# proc2.net
KiCad netlist of a schematic drawn in EAGLE
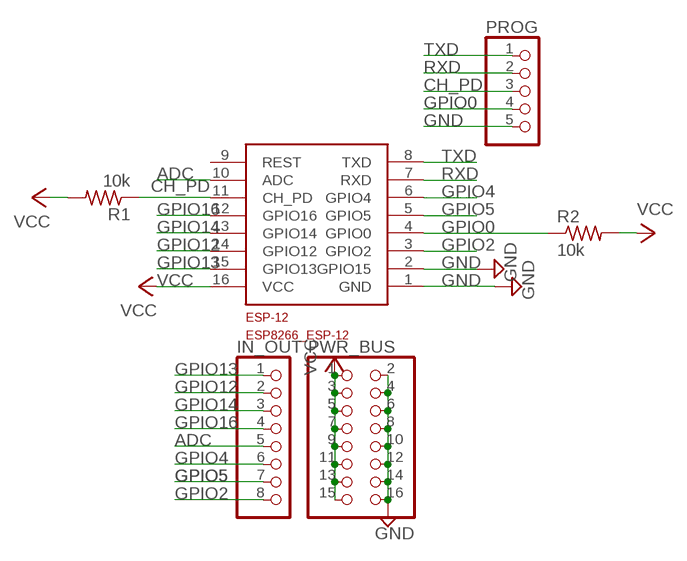
[diagram p0: schematic, sheet 1]

(export (version "E")
  (design (tool "Eeschema 10.0.6"))
  (components
    (comp (ref "ESP-12")
      (value "ESP8266_ESP-12")
      (footprint "eagle-import:ESP8266-ESP12")
      (libsource (lib "eagle-import") (part "ESP8266_ESP-12"))
    )
    (comp (ref "IN_OUT")
      (value "PINHD-1X8")
      (footprint "eagle-import:1X08")
      (libsource (lib "eagle-import") (part "PINHD-1X8"))
    )
    (comp (ref "PROG")
      (value "PINHD-1X5")
      (footprint "eagle-import:1X05")
      (libsource (lib "eagle-import") (part "PINHD-1X5"))
    )
    (comp (ref "PWR_BUS")
      (value "PINHD-2X8")
      (footprint "eagle-import:2X08")
      (libsource (lib "eagle-import") (part "PINHD-2X8"))
    )
    (comp (ref "R1")
      (value "10k")
      (footprint "eagle-import:M1206")
      (libsource (lib "eagle-import") (part "R-US_M1206"))
    )
    (comp (ref "R2")
      (value "10k")
      (footprint "eagle-import:M1206")
      (libsource (lib "eagle-import") (part "R-US_M1206"))
    )
  )
  (nets
    (net (code "1") (name "/ADC") (class "Default")
      (node (ref "ESP-12") (pin "10") (pinfunction "ADC_10") (pintype "bidirectional"))
      (node (ref "IN_OUT") (pin "5") (pinfunction "5_5") (pintype "passive"))
    )
    (net (code "2") (name "/CH_PD") (class "Default")
      (node (ref "ESP-12") (pin "11") (pinfunction "CH_PD_11") (pintype "bidirectional"))
      (node (ref "PROG") (pin "3") (pinfunction "3_3") (pintype "passive"))
      (node (ref "R1") (pin "1") (pinfunction "1_1") (pintype "passive"))
    )
    (net (code "3") (name "/GPIO0") (class "Default")
      (node (ref "ESP-12") (pin "4") (pinfunction "GPIO0_4") (pintype "bidirectional"))
      (node (ref "PROG") (pin "4") (pinfunction "4_4") (pintype "passive"))
      (node (ref "R2") (pin "1") (pinfunction "1_1") (pintype "passive"))
    )
    (net (code "4") (name "/GPIO2") (class "Default")
      (node (ref "ESP-12") (pin "3") (pinfunction "GPIO2_3") (pintype "bidirectional"))
      (node (ref "IN_OUT") (pin "8") (pinfunction "8_8") (pintype "passive"))
    )
    (net (code "5") (name "/GPIO4") (class "Default")
      (node (ref "ESP-12") (pin "6") (pinfunction "GPIO4_6") (pintype "bidirectional"))
      (node (ref "IN_OUT") (pin "6") (pinfunction "6_6") (pintype "passive"))
    )
    (net (code "6") (name "/GPIO5") (class "Default")
      (node (ref "ESP-12") (pin "5") (pinfunction "GPIO5_5") (pintype "bidirectional"))
      (node (ref "IN_OUT") (pin "7") (pinfunction "7_7") (pintype "passive"))
    )
    (net (code "7") (name "/GPIO12") (class "Default")
      (node (ref "ESP-12") (pin "14") (pinfunction "GPIO12_14") (pintype "bidirectional"))
      (node (ref "IN_OUT") (pin "2") (pinfunction "2_2") (pintype "passive"))
    )
    (net (code "8") (name "/GPIO13") (class "Default")
      (node (ref "ESP-12") (pin "15") (pinfunction "GPIO13_15") (pintype "bidirectional"))
      (node (ref "IN_OUT") (pin "1") (pinfunction "1_1") (pintype "passive"))
    )
    (net (code "9") (name "/GPIO14") (class "Default")
      (node (ref "ESP-12") (pin "13") (pinfunction "GPIO14_13") (pintype "bidirectional"))
      (node (ref "IN_OUT") (pin "3") (pinfunction "3_3") (pintype "passive"))
    )
    (net (code "10") (name "/GPIO16") (class "Default")
      (node (ref "ESP-12") (pin "12") (pinfunction "GPIO16_12") (pintype "bidirectional"))
      (node (ref "IN_OUT") (pin "4") (pinfunction "4_4") (pintype "passive"))
    )
    (net (code "11") (name "/RXD") (class "Default")
      (node (ref "ESP-12") (pin "7") (pinfunction "RXD_7") (pintype "bidirectional"))
      (node (ref "PROG") (pin "2") (pinfunction "2_2") (pintype "passive"))
    )
    (net (code "12") (name "/TXD") (class "Default")
      (node (ref "ESP-12") (pin "8") (pinfunction "TXD_8") (pintype "bidirectional"))
      (node (ref "PROG") (pin "1") (pinfunction "1_1") (pintype "passive"))
    )
    (net (code "13") (name "GND") (class "Default")
      (node (ref "ESP-12") (pin "1") (pinfunction "GND_1") (pintype "bidirectional"))
      (node (ref "ESP-12") (pin "2") (pinfunction "GPIO15_2") (pintype "bidirectional"))
      (node (ref "PROG") (pin "5") (pinfunction "5_5") (pintype "passive"))
      (node (ref "PWR_BUS") (pin "10") (pinfunction "10_10") (pintype "passive"))
      (node (ref "PWR_BUS") (pin "12") (pinfunction "12_12") (pintype "passive"))
      (node (ref "PWR_BUS") (pin "14") (pinfunction "14_14") (pintype "passive"))
      (node (ref "PWR_BUS") (pin "16") (pinfunction "16_16") (pintype "passive"))
      (node (ref "PWR_BUS") (pin "2") (pinfunction "2_2") (pintype "passive"))
      (node (ref "PWR_BUS") (pin "4") (pinfunction "4_4") (pintype "passive"))
      (node (ref "PWR_BUS") (pin "6") (pinfunction "6_6") (pintype "passive"))
      (node (ref "PWR_BUS") (pin "8") (pinfunction "8_8") (pintype "passive"))
    )
    (net (code "14") (name "VCC") (class "Default")
      (node (ref "ESP-12") (pin "16") (pinfunction "VCC_16") (pintype "bidirectional"))
      (node (ref "PWR_BUS") (pin "1") (pinfunction "1_1") (pintype "passive"))
      (node (ref "PWR_BUS") (pin "11") (pinfunction "11_11") (pintype "passive"))
      (node (ref "PWR_BUS") (pin "13") (pinfunction "13_13") (pintype "passive"))
      (node (ref "PWR_BUS") (pin "15") (pinfunction "15_15") (pintype "passive"))
      (node (ref "PWR_BUS") (pin "3") (pinfunction "3_3") (pintype "passive"))
      (node (ref "PWR_BUS") (pin "5") (pinfunction "5_5") (pintype "passive"))
      (node (ref "PWR_BUS") (pin "7") (pinfunction "7_7") (pintype "passive"))
      (node (ref "PWR_BUS") (pin "9") (pinfunction "9_9") (pintype "passive"))
      (node (ref "R1") (pin "2") (pinfunction "2_2") (pintype "passive"))
      (node (ref "R2") (pin "2") (pinfunction "2_2") (pintype "passive"))
    )
    (net (code "15") (name "unconnected-(ESP-12-REST-Pad9)") (class "Default")
      (node (ref "ESP-12") (pin "9") (pinfunction "REST_9") (pintype "bidirectional"))
    )
  )
)
